# PCB_Board4_schematic_2.net
KiCad netlist of a schematic drawn in Altium Designer
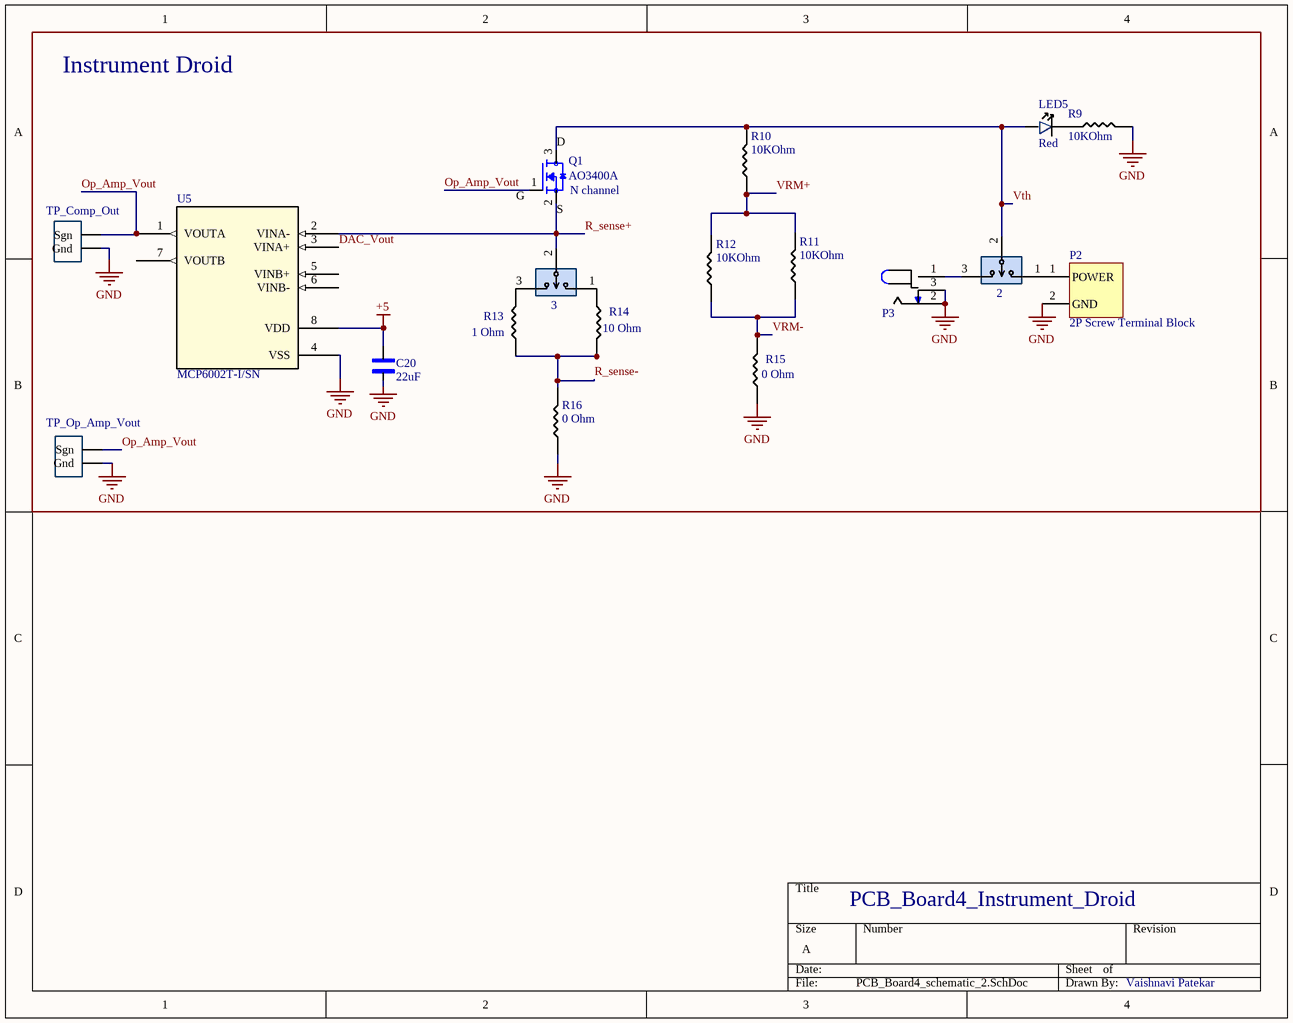
[diagram p0: PCB_Board4_schematic_2.SchDoc]

(export (version "E")
  (design (tool "Eeschema 10.0.6"))
  (components
    (comp (ref "2")
      (value "PREC003SAAN-RC")
      (footprint "3_PIN_100mil")
      (description "Connector Header Through Hole 3 position 0.100\" (2.54mm)")
      (fields (field (name "LCSC PART#") "C49257"))
      (libsource (lib "ECEN5730Lib_2023_01_DS") (part "SW_3Pin_100mil_Switch"))
    )
    (comp (ref "3")
      (value "PREC003SAAN-RC")
      (footprint "3_PIN_100mil")
      (description "Connector Header Through Hole 3 position 0.100\" (2.54mm)")
      (fields (field (name "LCSC PART#") "C49257"))
      (libsource (lib "ECEN5730Lib_2023_01_DS") (part "SW_3Pin_100mil_Switch"))
    )
    (comp (ref "C20")
      (value "22uF")
      (footprint "1206_Passive_Capacitor")
      (description "22uF ±10% 25V X5R 1206 Multilayer Ceramic Capacitors MLCC - SMD/SMT RoHS")
      (fields (field (name "MFR PART #") "CL31A226KAHNNNE") (field (name "LCSC PART#") "C12891"))
      (libsource (lib "ECEN5730Lib_2023_01_DS") (part "C_22uF_1206"))
    )
    (comp (ref "LED5")
      (value "Red")
      (footprint "LED_1206")
      (description "Red 621~631nm 1206 Light Emitting Diodes (LED) RoHS")
      (fields (field (name "MFR PART #") "15-21/R6C-FQ1R1B/2T") (field (name "LCSC PART#") "C93133"))
      (libsource (lib "ECEN5730Lib_2023_01_DS") (part "LED_RED_1206"))
    )
    (comp (ref "P2")
      (value "2P Screw Terminal Block")
      (footprint "P_Terminal block 3.5mm-pitch")
      (description "Green Straight pin 3.5mm  pitch; P=3.5mm  Screw terminal ROHS")
      (fields (field (name "MFR PART #") "KF350-3.5-2P") (field (name "MANUFACTURER") "Cixi Kefa Elec"))
      (libsource (lib "ECEN5730Lib_2023_01_DS") (part "P_Terminal block"))
    )
    (comp (ref "P3")
      (value "Power Jack")
      (footprint "Power_Jack")
      (description "Power Barrel Connector Jack 2.10mm ID (0.083\"), 5.50mm OD (0.217\") Through Hole, Right Angle")
      (fields (field (name "MFR PART #") "PJ-102A") (field (name "LCSC PART#") "C136744"))
      (libsource (lib "ECEN5730Lib_2023_01_DS") (part "P_Power Jack"))
    )
    (comp (ref "Q1")
      (value "AO3400A")
      (footprint "N-MOSFET")
      (description "MOSFET N Trench 30V 5.7A 1.5V @ 250uA 26.5 m? @ 5.7A,10V SOT-23-3L RoHS")
      (fields (field (name "LCSC PART#") "C20917") (field (name "ALTIUM_VALUE") "N channel"))
      (libsource (lib "ECEN5730Lib_2023_01_DS") (part "Q_Nch_MOSFET"))
    )
    (comp (ref "R9")
      (value "10KOhm")
      (footprint "1206_Passive_Resitor")
      (description "10 kOhms ±5% 0.25W, 1/4W Chip Resistor 1206 (3216 Metric) Automotive AEC-Q200 Thick Film")
      (fields (field (name "MFR PART #") "RMCF1206FT10K0") (field (name "LCSC PART#") "C17902"))
      (libsource (lib "ECEN5730Lib_2023_01_DS") (part "R_10KOhm_1206"))
    )
    (comp (ref "R10")
      (value "10KOhm")
      (footprint "1206_Passive_Resitor")
      (description "10 kOhms ±5% 0.25W, 1/4W Chip Resistor 1206 (3216 Metric) Automotive AEC-Q200 Thick Film")
      (fields (field (name "MFR PART #") "RMCF1206FT10K0") (field (name "LCSC PART#") "C17902"))
      (libsource (lib "ECEN5730Lib_2023_01_DS") (part "R_10KOhm_1206"))
    )
    (comp (ref "R11")
      (value "10KOhm")
      (footprint "1206_Passive_Resitor")
      (description "10 kOhms ±5% 0.25W, 1/4W Chip Resistor 1206 (3216 Metric) Automotive AEC-Q200 Thick Film")
      (fields (field (name "MFR PART #") "RMCF1206FT10K0") (field (name "LCSC PART#") "C17902"))
      (libsource (lib "ECEN5730Lib_2023_01_DS") (part "R_10KOhm_1206"))
    )
    (comp (ref "R12")
      (value "10KOhm")
      (footprint "1206_Passive_Resitor")
      (description "10 kOhms ±5% 0.25W, 1/4W Chip Resistor 1206 (3216 Metric) Automotive AEC-Q200 Thick Film")
      (fields (field (name "MFR PART #") "RMCF1206FT10K0") (field (name "LCSC PART#") "C17902"))
      (libsource (lib "ECEN5730Lib_2023_01_DS") (part "R_10KOhm_1206"))
    )
    (comp (ref "R13")
      (value "1 Ohm")
      (footprint "1206_Passive_Resitor")
      (description "1Ω ±5% 0.25W ±400ppm/℃ 1206 Chip Resistor - Surface Mount RoHS")
      (fields (field (name "LCSC PART#") "C1409") (field (name "MFR PART #") "1206W4J010JT5E"))
      (libsource (lib "ECEN5730Lib_2023_01_DS") (part "R_1Ohm_1206"))
    )
    (comp (ref "R14")
      (value "10 Ohm")
      (footprint "1206_Passive_Resitor")
      (description "CHIP RESISTOR - SURFACE MOUNT 0.1OHMS ±1% 1/4W 1206 ROHS")
      (fields (field (name "MFR PART #") "1206W4F100JT5E") (field (name "LCSC PART#") "C17903"))
      (libsource (lib "ECEN5730Lib_2023_01_DS") (part "R_10Ohm_1206"))
    )
    (comp (ref "R15")
      (value "0 Ohm")
      (footprint "1206_Passive_Resitor")
      (description "CHIP RESISTOR - SURFACE MOUNT 0OHMS ±1% 1/4W 1206 ROHS")
      (fields (field (name "MFR PART #") "1206W4F0000T5E") (field (name "LCSC PART#") "C17888"))
      (libsource (lib "ECEN5730Lib_2023_01_DS") (part "R_0Ohm_1206"))
    )
    (comp (ref "R16")
      (value "0 Ohm")
      (footprint "1206_Passive_Resitor")
      (description "CHIP RESISTOR - SURFACE MOUNT 0OHMS ±1% 1/4W 1206 ROHS")
      (fields (field (name "MFR PART #") "1206W4F0000T5E") (field (name "LCSC PART#") "C17888"))
      (libsource (lib "ECEN5730Lib_2023_01_DS") (part "R_0Ohm_1206"))
    )
    (comp (ref "TP14")
      (value "TP_Comp_Out")
      (footprint "TP10x_Probe")
      (description "Test Point 300 mil centers")
      (libsource (lib "ECEN5730Lib_2023_01_DS") (part "TP_10x_Probe"))
    )
    (comp (ref "TP15")
      (value "TP_Op_Amp_Vout")
      (footprint "TP10x_Probe")
      (description "Test Point 300 mil centers")
      (libsource (lib "ECEN5730Lib_2023_01_DS") (part "TP_10x_Probe"))
    )
    (comp (ref "U5")
      (value "MCP6002T-I/SN")
      (footprint "SOIC127P600X175-8N")
      (description "0.6 V/us 2 1MHz 1.8V ~ 6V 100μA General Purpose SOIC-8_150mil  Operational Amplifier ROHS")
      (fields (field (name "MFR") "Microchip") (field (name "LCSC PART#") "C7377"))
      (libsource (lib "ECEN5730Lib_2023_01_DS") (part "U_MCP6002T-I/SN"))
    )
  )
  (nets
    (net (code "1") (name "+5") (class "Default")
      (node (ref "C20") (pin "1") (pinfunction "1_1") (pintype "passive"))
      (node (ref "U5") (pin "8") (pinfunction "VDD_8") (pintype "passive"))
    )
    (net (code "2") (name "/DAC_Vout") (class "Default")
      (node (ref "U5") (pin "3") (pinfunction "VINA+_3") (pintype "input"))
    )
    (net (code "3") (name "/Op_Amp_Vout") (class "Default")
      (node (ref "Q1") (pin "1") (pinfunction "G_1") (pintype "passive"))
      (node (ref "TP14") (pin "1") (pinfunction "Sgn_1") (pintype "passive"))
      (node (ref "TP15") (pin "1") (pinfunction "Sgn_1") (pintype "passive"))
      (node (ref "U5") (pin "1") (pinfunction "VOUTA_1") (pintype "output"))
    )
    (net (code "4") (name "/R_sense+") (class "Default")
      (node (ref "3") (pin "2") (pinfunction "2_2") (pintype "passive"))
      (node (ref "Q1") (pin "2") (pinfunction "S_2") (pintype "passive"))
      (node (ref "U5") (pin "2") (pinfunction "VINA-_2") (pintype "input"))
    )
    (net (code "5") (name "/R_sense-") (class "Default")
      (node (ref "R13") (pin "1") (pinfunction "1_1") (pintype "passive"))
      (node (ref "R14") (pin "2") (pinfunction "2_2") (pintype "passive"))
      (node (ref "R16") (pin "2") (pinfunction "2_2") (pintype "passive"))
    )
    (net (code "6") (name "/VRM+") (class "Default")
      (node (ref "R10") (pin "1") (pinfunction "1_1") (pintype "passive"))
      (node (ref "R11") (pin "2") (pinfunction "2_2") (pintype "passive"))
      (node (ref "R12") (pin "2") (pinfunction "2_2") (pintype "passive"))
    )
    (net (code "7") (name "/VRM-") (class "Default")
      (node (ref "R11") (pin "1") (pinfunction "1_1") (pintype "passive"))
      (node (ref "R12") (pin "1") (pinfunction "1_1") (pintype "passive"))
      (node (ref "R15") (pin "2") (pinfunction "2_2") (pintype "passive"))
    )
    (net (code "8") (name "/Vth") (class "Default")
      (node (ref "2") (pin "2") (pinfunction "2_2") (pintype "passive"))
      (node (ref "LED5") (pin "1") (pinfunction "1_1") (pintype "passive"))
      (node (ref "Q1") (pin "3") (pinfunction "D_3") (pintype "passive"))
      (node (ref "R10") (pin "2") (pinfunction "2_2") (pintype "passive"))
    )
    (net (code "9") (name "GND") (class "Default")
      (node (ref "C20") (pin "2") (pinfunction "2_2") (pintype "passive"))
      (node (ref "P2") (pin "2") (pinfunction "GND_2") (pintype "passive"))
      (node (ref "P3") (pin "2") (pinfunction "2_2") (pintype "power_in"))
      (node (ref "P3") (pin "3") (pinfunction "3_3") (pintype "power_in"))
      (node (ref "R15") (pin "1") (pinfunction "1_1") (pintype "passive"))
      (node (ref "R16") (pin "1") (pinfunction "1_1") (pintype "passive"))
      (node (ref "R9") (pin "2") (pinfunction "2_2") (pintype "passive"))
      (node (ref "TP14") (pin "2") (pinfunction "Gnd_2") (pintype "passive"))
      (node (ref "TP15") (pin "2") (pinfunction "Gnd_2") (pintype "passive"))
      (node (ref "U5") (pin "4") (pinfunction "VSS_4") (pintype "passive"))
    )
    (net (code "10") (name "Net-(2-Pad3)") (class "Default")
      (node (ref "2") (pin "3") (pinfunction "3_3") (pintype "passive"))
      (node (ref "P3") (pin "1") (pinfunction "1_1") (pintype "power_in"))
    )
    (net (code "11") (name "Net-(3-Pad1)") (class "Default")
      (node (ref "3") (pin "1") (pinfunction "1_1") (pintype "passive"))
      (node (ref "R14") (pin "1") (pinfunction "1_1") (pintype "passive"))
    )
    (net (code "12") (name "Net-(3-Pad3)") (class "Default")
      (node (ref "3") (pin "3") (pinfunction "3_3") (pintype "passive"))
      (node (ref "R13") (pin "2") (pinfunction "2_2") (pintype "passive"))
    )
    (net (code "13") (name "Net-(LED5-Pad2)") (class "Default")
      (node (ref "LED5") (pin "2") (pinfunction "2_2") (pintype "passive"))
      (node (ref "R9") (pin "1") (pinfunction "1_1") (pintype "passive"))
    )
    (net (code "14") (name "Net-(P2-POWER)") (class "Default")
      (node (ref "2") (pin "1") (pinfunction "1_1") (pintype "passive"))
      (node (ref "P2") (pin "1") (pinfunction "POWER_1") (pintype "passive"))
    )
    (net (code "15") (name "unconnected-(U5-VINB+-Pad5)") (class "Default")
      (node (ref "U5") (pin "5") (pinfunction "VINB+_5") (pintype "input"))
    )
    (net (code "16") (name "unconnected-(U5-VINB--Pad6)") (class "Default")
      (node (ref "U5") (pin "6") (pinfunction "VINB-_6") (pintype "input"))
    )
    (net (code "17") (name "unconnected-(U5-VOUTB-Pad7)") (class "Default")
      (node (ref "U5") (pin "7") (pinfunction "VOUTB_7") (pintype "output"))
    )
  )
)
